# OLED-0_96-Demo-MCU_Board.net
KiCad netlist of a schematic drawn in Altium Designer
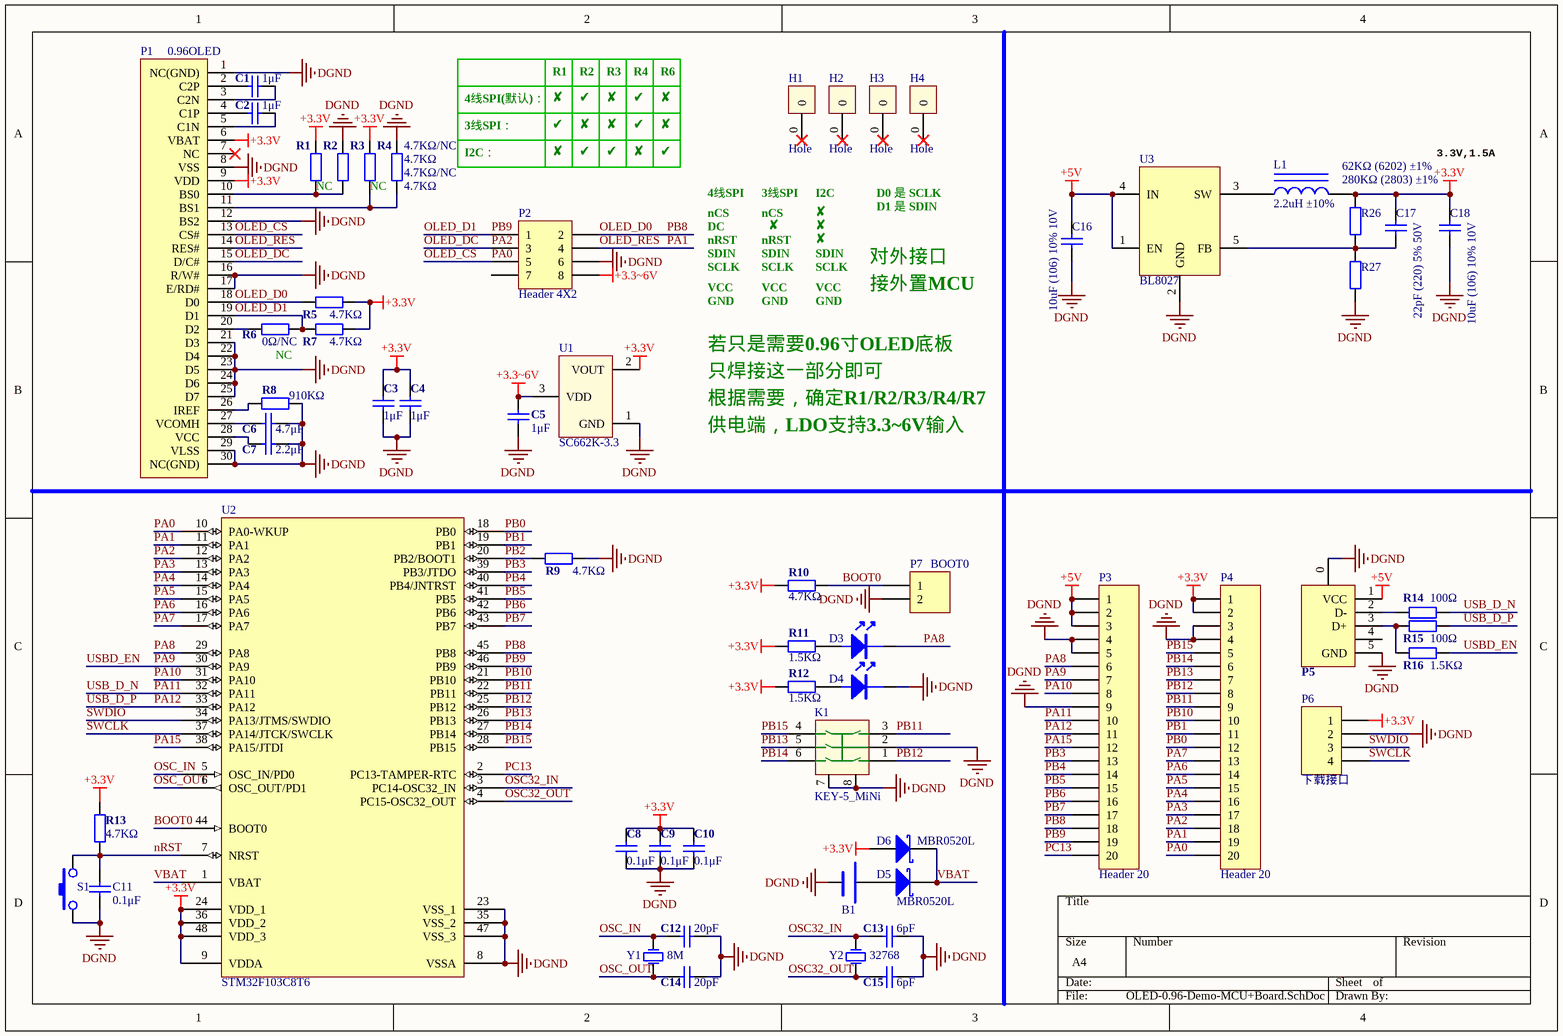
[diagram p0: OLED-0.96-Demo-MCU+Board.SchDoc]

(export (version "E")
  (design (tool "Eeschema 10.0.6"))
  (components
    (comp (ref "B1")
      (value "BAT")
      (footprint "BATTERY SOCKET")
      (description "电池")
      (libsource (lib "OLED-0.96-Demo-MCU+Board") (part "BAT"))
    )
    (comp (ref "C1")
      (value "1μF")
      (footprint "LC-0603_C")
      (description "贴片电容")
      (libsource (lib "FourAxis") (part "Cap"))
    )
    (comp (ref "C2")
      (value "1μF")
      (footprint "LC-0603_C")
      (description "贴片电容")
      (libsource (lib "FourAxis") (part "Cap"))
    )
    (comp (ref "C3")
      (value "1μF")
      (footprint "LC-0603_C")
      (description "贴片电容")
      (libsource (lib "FourAxis") (part "Cap"))
    )
    (comp (ref "C4")
      (value "1μF")
      (footprint "LC-0603_C")
      (description "贴片电容")
      (libsource (lib "FourAxis") (part "Cap"))
    )
    (comp (ref "C5")
      (value "1μF")
      (footprint "LC-0603_C")
      (description "贴片电容")
      (libsource (lib "FourAxis") (part "Cap"))
    )
    (comp (ref "C6")
      (value "4.7μF")
      (footprint "LC-0603_C")
      (description "贴片电容")
      (libsource (lib "FourAxis") (part "Cap"))
    )
    (comp (ref "C7")
      (value "2.2μF")
      (footprint "LC-0603_C")
      (description "贴片电容")
      (libsource (lib "FourAxis") (part "Cap"))
    )
    (comp (ref "C8")
      (value "0.1μF")
      (footprint "LC-0603_C")
      (description "贴片电容")
      (libsource (lib "FourAxis") (part "Cap"))
    )
    (comp (ref "C9")
      (value "0.1μF")
      (footprint "LC-0603_C")
      (description "贴片电容")
      (libsource (lib "FourAxis") (part "Cap"))
    )
    (comp (ref "C10")
      (value "0.1μF")
      (footprint "LC-0603_C")
      (description "贴片电容")
      (libsource (lib "FourAxis") (part "Cap"))
    )
    (comp (ref "C11")
      (value "0.1μF")
      (footprint "LC-0603_C")
      (description "贴片电容")
      (libsource (lib "FourAxis") (part "Cap"))
    )
    (comp (ref "C12")
      (value "20pF")
      (footprint "LC-0603_C")
      (description "贴片电容")
      (libsource (lib "FourAxis") (part "Cap"))
    )
    (comp (ref "C13")
      (value "6pF")
      (footprint "LC-0603_C")
      (description "贴片电容")
      (libsource (lib "FourAxis") (part "Cap"))
    )
    (comp (ref "C14")
      (value "20pF")
      (footprint "LC-0603_C")
      (description "贴片电容")
      (libsource (lib "FourAxis") (part "Cap"))
    )
    (comp (ref "C15")
      (value "6pF")
      (footprint "LC-0603_C")
      (description "贴片电容")
      (libsource (lib "FourAxis") (part "Cap"))
    )
    (comp (ref "C16")
      (value "10uF (106) 10% 10V")
      (footprint "LC-0603_C")
      (description "贴片电容")
      (libsource (lib "Miscellaneous Devices LC") (part "0603 10uF (106) 10% 10V"))
    )
    (comp (ref "C17")
      (value "22pF (220) 5% 50V")
      (footprint "LC-0603_C")
      (description "贴片电容")
      (libsource (lib "Miscellaneous Devices LC") (part "0402 22pF (220) 5% 50V"))
    )
    (comp (ref "C18")
      (value "10uF (106) 10% 10V")
      (footprint "LC-0603_C")
      (description "贴片电容")
      (libsource (lib "Miscellaneous Devices LC") (part "0603 10uF (106) 10% 10V"))
    )
    (comp (ref "D3")
      (value "POWER")
      (footprint "LC-0603_LED_S1")
      (description "发光二极管")
      (libsource (lib "OLED-0.96-Demo-MCU+Board") (part "LED1"))
    )
    (comp (ref "D4")
      (value "POWER")
      (footprint "LC-0603_LED_S1")
      (description "发光二极管")
      (libsource (lib "OLED-0.96-Demo-MCU+Board") (part "LED1"))
    )
    (comp (ref "D5")
      (value "MBR0520L")
      (footprint "LC-SOD-123")
      (description "贴片肖特基二极管")
      (fields (field (name "PUBLISHER") "Altium Limited"))
      (libsource (lib "USB-UART-RJ45") (part "Diode 18TQ045"))
    )
    (comp (ref "D6")
      (value "MBR0520L")
      (footprint "LC-SOD-123")
      (description "贴片肖特基二极管")
      (fields (field (name "PUBLISHER") "Altium Limited"))
      (libsource (lib "USB-UART-RJ45") (part "Diode 18TQ045"))
    )
    (comp (ref "H1")
      (value "Hole")
      (footprint "Hole")
      (description "螺丝孔")
      (libsource (lib "VGA_2") (part "Hole"))
    )
    (comp (ref "H2")
      (value "Hole")
      (footprint "Hole")
      (description "螺丝孔")
      (libsource (lib "VGA_2") (part "Hole"))
    )
    (comp (ref "H3")
      (value "Hole")
      (footprint "Hole")
      (description "螺丝孔")
      (libsource (lib "VGA_2") (part "Hole"))
    )
    (comp (ref "H4")
      (value "Hole")
      (footprint "Hole")
      (description "螺丝孔")
      (libsource (lib "VGA_2") (part "Hole"))
    )
    (comp (ref "K1")
      (value "KEY-5_MiNi")
      (footprint "KEY_5_mini")
      (description "贴片五向开关")
      (libsource (lib "OLED-0.96-Demo-MCU+Board") (part "KEY-5_MiNi"))
    )
    (comp (ref "L1")
      (value "2.2uH ±10%")
      (footprint "LC-0805_L")
      (description "贴片电感")
      (libsource (lib "Miscellaneous Devices LC") (part "0805 2.2uH 10%"))
    )
    (comp (ref "P1")
      (value "0.96OLED")
      (footprint "OLED_0.96")
      (description "接口")
      (fields (field (name "PUBLISHER") "Altium Limited"))
      (libsource (lib "HLW8012-Demo") (part "0.96OLED"))
    )
    (comp (ref "P2")
      (value "Header 4X2")
      (footprint "2*4P_SMT")
      (description "Header, 4-Pin, Dual row")
      (fields (field (name "PUBLISHER") "Altium Limited"))
      (libsource (lib "Miscellaneous Connectors") (part "Header 4X2"))
    )
    (comp (ref "P3")
      (value "Header 20")
      (footprint "HDR1X20")
      (description "Header, 20-Pin")
      (fields (field (name "PUBLISHER") "Altium Limited"))
      (libsource (lib "Miscellaneous Connectors") (part "Header 20"))
    )
    (comp (ref "P4")
      (value "Header 20")
      (footprint "HDR1X20")
      (description "Header, 20-Pin")
      (fields (field (name "PUBLISHER") "Altium Limited"))
      (libsource (lib "Miscellaneous Connectors") (part "Header 20"))
    )
    (comp (ref "P5")
      (value "Micro USB,母头")
      (footprint "MicroUSB2")
      (description "接口")
      (libsource (lib "SU-IOT_v2.0") (part "microUSB"))
    )
    (comp (ref "P6")
      (value "下载接口")
      (footprint "HDR1X4")
      (description "Header, 4-Pin")
      (fields (field (name "PUBLISHER") "Altium Limited"))
      (libsource (lib "Miscellaneous Connectors") (part "Header 4"))
    )
    (comp (ref "P7")
      (value "BOOT0")
      (footprint "HDR1X2")
      (description "Header, 2-Pin")
      (fields (field (name "PUBLISHER") "Altium Limited"))
      (libsource (lib "Miscellaneous Connectors") (part "Header 2"))
    )
    (comp (ref "R1")
      (value "4.7KΩ/NC")
      (footprint "LC-0603_R")
      (description "贴片电阻")
      (libsource (lib "") (part "电阻_2"))
    )
    (comp (ref "R2")
      (value "4.7KΩ")
      (footprint "LC-0603_R")
      (description "贴片电阻")
      (libsource (lib "") (part "电阻_2"))
    )
    (comp (ref "R3")
      (value "4.7KΩ/NC")
      (footprint "LC-0603_R")
      (description "贴片电阻")
      (libsource (lib "") (part "电阻_1"))
    )
    (comp (ref "R4")
      (value "4.7KΩ")
      (footprint "LC-0603_R")
      (description "贴片电阻")
      (libsource (lib "") (part "电阻_1"))
    )
    (comp (ref "R5")
      (value "4.7KΩ")
      (footprint "LC-0603_R")
      (description "贴片电阻")
      (libsource (lib "FourAxis") (part "电阻"))
    )
    (comp (ref "R6")
      (value "0Ω/NC")
      (footprint "LC-0603_R")
      (description "贴片电阻")
      (libsource (lib "") (part "电阻_1"))
    )
    (comp (ref "R7")
      (value "4.7KΩ")
      (footprint "LC-0603_R")
      (description "贴片电阻")
      (libsource (lib "FourAxis") (part "电阻"))
    )
    (comp (ref "R8")
      (value "910KΩ")
      (footprint "LC-0603_R")
      (description "贴片电阻")
      (libsource (lib "") (part "电阻_1"))
    )
    (comp (ref "R9")
      (value "4.7KΩ")
      (footprint "LC-0603_R")
      (description "贴片电阻")
      (libsource (lib "FourAxis") (part "电阻"))
    )
    (comp (ref "R10")
      (value "4.7KΩ")
      (footprint "LC-0603_R")
      (description "贴片电阻")
      (libsource (lib "FourAxis") (part "电阻"))
    )
    (comp (ref "R11")
      (value "1.5KΩ")
      (footprint "LC-0603_R")
      (description "贴片电阻")
      (libsource (lib "FourAxis") (part "电阻"))
    )
    (comp (ref "R12")
      (value "1.5KΩ")
      (footprint "LC-0603_R")
      (description "贴片电阻")
      (libsource (lib "FourAxis") (part "电阻"))
    )
    (comp (ref "R13")
      (value "4.7KΩ")
      (footprint "LC-0603_R")
      (description "贴片电阻")
      (libsource (lib "") (part "电阻_2"))
    )
    (comp (ref "R14")
      (value "100Ω")
      (footprint "LC-0603_R")
      (description "贴片电阻")
      (libsource (lib "FourAxis") (part "电阻"))
    )
    (comp (ref "R15")
      (value "100Ω")
      (footprint "LC-0603_R")
      (description "贴片电阻")
      (libsource (lib "FourAxis") (part "电阻"))
    )
    (comp (ref "R16")
      (value "1.5KΩ")
      (footprint "LC-0603_R")
      (description "贴片电阻")
      (libsource (lib "FourAxis") (part "电阻"))
    )
    (comp (ref "R26")
      (value "280KΩ (2803) ±1%")
      (footprint "LC-0603_R")
      (description "贴片电阻")
      (libsource (lib "") (part "0805 62KΩ (6202) 1%_1"))
    )
    (comp (ref "R27")
      (value "62KΩ (6202) ±1%")
      (footprint "LC-0603_R")
      (description "贴片电阻")
      (libsource (lib "Miscellaneous Devices LC") (part "0805 62KΩ (6202) 1%"))
    )
    (comp (ref "S1")
      (value "微动开关")
      (footprint "按键")
      (libsource (lib "OLED-0.96-Demo-MCU+Board") (part "微动开关"))
    )
    (comp (ref "U1")
      (value "SC662K-3.3")
      (footprint "LC-SOT-23(SOT-23-3)")
      (description "IC")
      (libsource (lib "HLW8012-Demo") (part "SC662K-3.3"))
    )
    (comp (ref "U2")
      (value "STM32F103C8T6")
      (footprint "LC-LQFP-48_7x7x05P")
      (description "IC")
      (fields (field (name "PUBLISHER") "Altium Limited"))
      (libsource (lib "FourAxis") (part "STM32F103CBT6"))
    )
    (comp (ref "U3")
      (value "BL8027")
      (footprint "LC-SOT-23-5")
      (description "IC")
      (libsource (lib "OLED-0.96-Demo-MCU+Board") (part "DC-DC"))
    )
    (comp (ref "Y1")
      (value "8M")
      (footprint "LC-HC-49SMD")
      (description "晶振（直插）")
      (fields (field (name "PUBLISHER") "Altium Limited"))
      (libsource (lib "") (part "XTAL_1_1"))
    )
    (comp (ref "Y2")
      (value "32768")
      (footprint "MC-306")
      (description "晶振（直插）")
      (fields (field (name "PUBLISHER") "Altium Limited"))
      (libsource (lib "OLED-0.96-Demo-MCU+Board") (part "XTAL_1"))
    )
  )
  (nets
    (net (code "1") (name "+3.3V") (class "Default")
      (node (ref "C10") (pin "2") (pinfunction "2_2") (pintype "passive"))
      (node (ref "C17") (pin "2") (pinfunction "2_2") (pintype "passive"))
      (node (ref "C18") (pin "2") (pinfunction "2_2") (pintype "passive"))
      (node (ref "C3") (pin "2") (pinfunction "2_2") (pintype "passive"))
      (node (ref "C4") (pin "2") (pinfunction "2_2") (pintype "passive"))
      (node (ref "C8") (pin "2") (pinfunction "2_2") (pintype "passive"))
      (node (ref "C9") (pin "2") (pinfunction "2_2") (pintype "passive"))
      (node (ref "D6") (pin "1") (pinfunction "A_1") (pintype "passive"))
      (node (ref "L1") (pin "2") (pinfunction "2_2") (pintype "passive"))
      (node (ref "P1") (pin "6") (pinfunction "VBAT_6") (pintype "passive"))
      (node (ref "P1") (pin "9") (pinfunction "VDD_9") (pintype "passive"))
      (node (ref "P4") (pin "1") (pinfunction "1_1") (pintype "passive"))
      (node (ref "P4") (pin "2") (pinfunction "2_2") (pintype "passive"))
      (node (ref "P6") (pin "1") (pinfunction "1_1") (pintype "passive"))
      (node (ref "R1") (pin "2") (pinfunction "2_2") (pintype "passive"))
      (node (ref "R10") (pin "2") (pinfunction "2_2") (pintype "passive"))
      (node (ref "R11") (pin "2") (pinfunction "2_2") (pintype "passive"))
      (node (ref "R12") (pin "2") (pinfunction "2_2") (pintype "passive"))
      (node (ref "R13") (pin "2") (pinfunction "2_2") (pintype "passive"))
      (node (ref "R26") (pin "1") (pinfunction "1_1") (pintype "passive"))
      (node (ref "R3") (pin "1") (pinfunction "1_1") (pintype "passive"))
      (node (ref "R5") (pin "1") (pinfunction "1_1") (pintype "passive"))
      (node (ref "R7") (pin "1") (pinfunction "1_1") (pintype "passive"))
      (node (ref "U1") (pin "2") (pinfunction "VOUT_2") (pintype "passive"))
      (node (ref "U2") (pin "24") (pinfunction "VDD_1_24") (pintype "power_in"))
      (node (ref "U2") (pin "36") (pinfunction "VDD_2_36") (pintype "power_in"))
      (node (ref "U2") (pin "48") (pinfunction "VDD_3_48") (pintype "power_in"))
      (node (ref "U2") (pin "9") (pinfunction "VDDA_9") (pintype "power_in"))
    )
    (net (code "2") (name "+3.3~6V") (class "Default")
      (node (ref "C5") (pin "1") (pinfunction "1_1") (pintype "passive"))
      (node (ref "P2") (pin "8") (pinfunction "8_8") (pintype "passive"))
      (node (ref "U1") (pin "3") (pinfunction "VDD_3") (pintype "passive"))
    )
    (net (code "3") (name "+5V") (class "Default")
      (node (ref "C16") (pin "2") (pinfunction "2_2") (pintype "passive"))
      (node (ref "P3") (pin "1") (pinfunction "1_1") (pintype "passive"))
      (node (ref "P3") (pin "2") (pinfunction "2_2") (pintype "passive"))
      (node (ref "P3") (pin "3") (pinfunction "3_3") (pintype "passive"))
      (node (ref "P5") (pin "1") (pinfunction "VCC_1") (pintype "passive"))
      (node (ref "U3") (pin "1") (pinfunction "EN_1") (pintype "passive"))
      (node (ref "U3") (pin "4") (pinfunction "IN_4") (pintype "passive"))
    )
    (net (code "4") (name "/BOOT0") (class "Default")
      (node (ref "P7") (pin "1") (pinfunction "1_1") (pintype "passive"))
      (node (ref "R10") (pin "1") (pinfunction "1_1") (pintype "passive"))
      (node (ref "U2") (pin "44") (pinfunction "BOOT0_44") (pintype "input"))
    )
    (net (code "5") (name "/OLED_CS") (class "Default")
      (node (ref "P1") (pin "13") (pinfunction "CS#_13") (pintype "passive"))
      (node (ref "P2") (pin "5") (pinfunction "5_5") (pintype "passive"))
      (node (ref "P4") (pin "20") (pinfunction "20_20") (pintype "passive"))
      (node (ref "U2") (pin "10") (pinfunction "PA0-WKUP_10") (pintype "bidirectional"))
    )
    (net (code "6") (name "/OLED_D0") (class "Default")
      (node (ref "P1") (pin "18") (pinfunction "D0_18") (pintype "passive"))
      (node (ref "P2") (pin "2") (pinfunction "2_2") (pintype "passive"))
      (node (ref "P3") (pin "18") (pinfunction "18_18") (pintype "passive"))
      (node (ref "R5") (pin "2") (pinfunction "2_2") (pintype "passive"))
      (node (ref "U2") (pin "45") (pinfunction "PB8_45") (pintype "bidirectional"))
    )
    (net (code "7") (name "/OLED_D1") (class "Default")
      (node (ref "P1") (pin "19") (pinfunction "D1_19") (pintype "passive"))
      (node (ref "P2") (pin "1") (pinfunction "1_1") (pintype "passive"))
      (node (ref "P3") (pin "19") (pinfunction "19_19") (pintype "passive"))
      (node (ref "R6") (pin "1") (pinfunction "1_1") (pintype "passive"))
      (node (ref "R7") (pin "2") (pinfunction "2_2") (pintype "passive"))
      (node (ref "U2") (pin "46") (pinfunction "PB9_46") (pintype "bidirectional"))
    )
    (net (code "8") (name "/OLED_DC") (class "Default")
      (node (ref "P1") (pin "15") (pinfunction "D/C#_15") (pintype "passive"))
      (node (ref "P2") (pin "3") (pinfunction "3_3") (pintype "passive"))
      (node (ref "P4") (pin "18") (pinfunction "18_18") (pintype "passive"))
      (node (ref "U2") (pin "12") (pinfunction "PA2_12") (pintype "bidirectional"))
    )
    (net (code "9") (name "/OLED_RES") (class "Default")
      (node (ref "P1") (pin "14") (pinfunction "RES#_14") (pintype "passive"))
      (node (ref "P2") (pin "4") (pinfunction "4_4") (pintype "passive"))
      (node (ref "P4") (pin "19") (pinfunction "19_19") (pintype "passive"))
      (node (ref "U2") (pin "11") (pinfunction "PA1_11") (pintype "bidirectional"))
    )
    (net (code "10") (name "/OSC32_IN") (class "Default")
      (node (ref "C13") (pin "1") (pinfunction "1_1") (pintype "passive"))
      (node (ref "U2") (pin "3") (pinfunction "PC14-OSC32_IN_3") (pintype "bidirectional"))
      (node (ref "Y2") (pin "1") (pinfunction "1_1") (pintype "passive"))
    )
    (net (code "11") (name "/OSC32_OUT") (class "Default")
      (node (ref "C15") (pin "1") (pinfunction "1_1") (pintype "passive"))
      (node (ref "U2") (pin "4") (pinfunction "PC15-OSC32_OUT_4") (pintype "bidirectional"))
      (node (ref "Y2") (pin "4") (pinfunction "4_4") (pintype "passive"))
    )
    (net (code "12") (name "/OSC_IN") (class "Default")
      (node (ref "C12") (pin "1") (pinfunction "1_1") (pintype "passive"))
      (node (ref "U2") (pin "5") (pinfunction "OSC_IN/PD0_5") (pintype "input"))
      (node (ref "Y1") (pin "1") (pinfunction "1_1") (pintype "passive"))
    )
    (net (code "13") (name "/OSC_OUT") (class "Default")
      (node (ref "C14") (pin "1") (pinfunction "1_1") (pintype "passive"))
      (node (ref "U2") (pin "6") (pinfunction "OSC_OUT/PD1_6") (pintype "output"))
      (node (ref "Y1") (pin "2") (pinfunction "2_2") (pintype "passive"))
    )
    (net (code "14") (name "/PA3") (class "Default")
      (node (ref "P4") (pin "17") (pinfunction "17_17") (pintype "passive"))
      (node (ref "U2") (pin "13") (pinfunction "PA3_13") (pintype "bidirectional"))
    )
    (net (code "15") (name "/PA4") (class "Default")
      (node (ref "P4") (pin "16") (pinfunction "16_16") (pintype "passive"))
      (node (ref "U2") (pin "14") (pinfunction "PA4_14") (pintype "bidirectional"))
    )
    (net (code "16") (name "/PA5") (class "Default")
      (node (ref "P4") (pin "15") (pinfunction "15_15") (pintype "passive"))
      (node (ref "U2") (pin "15") (pinfunction "PA5_15") (pintype "bidirectional"))
    )
    (net (code "17") (name "/PA6") (class "Default")
      (node (ref "P4") (pin "14") (pinfunction "14_14") (pintype "passive"))
      (node (ref "U2") (pin "16") (pinfunction "PA6_16") (pintype "bidirectional"))
    )
    (net (code "18") (name "/PA7") (class "Default")
      (node (ref "P4") (pin "13") (pinfunction "13_13") (pintype "passive"))
      (node (ref "U2") (pin "17") (pinfunction "PA7_17") (pintype "bidirectional"))
    )
    (net (code "19") (name "/PA8") (class "Default")
      (node (ref "D3") (pin "K") (pinfunction "K_K") (pintype "passive"))
      (node (ref "P3") (pin "6") (pinfunction "6_6") (pintype "passive"))
      (node (ref "U2") (pin "29") (pinfunction "PA8_29") (pintype "bidirectional"))
    )
    (net (code "20") (name "/PA9") (class "Default")
      (node (ref "P3") (pin "7") (pinfunction "7_7") (pintype "passive"))
      (node (ref "R16") (pin "1") (pinfunction "1_1") (pintype "passive"))
      (node (ref "U2") (pin "30") (pinfunction "PA9_30") (pintype "bidirectional"))
    )
    (net (code "21") (name "/PA10") (class "Default")
      (node (ref "P3") (pin "8") (pinfunction "8_8") (pintype "passive"))
      (node (ref "U2") (pin "31") (pinfunction "PA10_31") (pintype "bidirectional"))
    )
    (net (code "22") (name "/PA11") (class "Default")
      (node (ref "P3") (pin "10") (pinfunction "10_10") (pintype "passive"))
      (node (ref "R14") (pin "1") (pinfunction "1_1") (pintype "passive"))
      (node (ref "U2") (pin "32") (pinfunction "PA11_32") (pintype "bidirectional"))
    )
    (net (code "23") (name "/PA12") (class "Default")
      (node (ref "P3") (pin "11") (pinfunction "11_11") (pintype "passive"))
      (node (ref "R15") (pin "1") (pinfunction "1_1") (pintype "passive"))
      (node (ref "U2") (pin "33") (pinfunction "PA12_33") (pintype "bidirectional"))
    )
    (net (code "24") (name "/PA15") (class "Default")
      (node (ref "P3") (pin "12") (pinfunction "12_12") (pintype "passive"))
      (node (ref "U2") (pin "38") (pinfunction "PA15/JTDI_38") (pintype "bidirectional"))
    )
    (net (code "25") (name "/PB0") (class "Default")
      (node (ref "P4") (pin "12") (pinfunction "12_12") (pintype "passive"))
      (node (ref "U2") (pin "18") (pinfunction "PB0_18") (pintype "bidirectional"))
    )
    (net (code "26") (name "/PB1") (class "Default")
      (node (ref "P4") (pin "11") (pinfunction "11_11") (pintype "passive"))
      (node (ref "U2") (pin "19") (pinfunction "PB1_19") (pintype "bidirectional"))
    )
    (net (code "27") (name "/PB2") (class "Default")
      (node (ref "R9") (pin "2") (pinfunction "2_2") (pintype "passive"))
      (node (ref "U2") (pin "20") (pinfunction "PB2/BOOT1_20") (pintype "bidirectional"))
    )
    (net (code "28") (name "/PB3") (class "Default")
      (node (ref "P3") (pin "13") (pinfunction "13_13") (pintype "passive"))
      (node (ref "U2") (pin "39") (pinfunction "PB3/JTDO_39") (pintype "bidirectional"))
    )
    (net (code "29") (name "/PB4") (class "Default")
      (node (ref "P3") (pin "14") (pinfunction "14_14") (pintype "passive"))
      (node (ref "U2") (pin "40") (pinfunction "PB4/JNTRST_40") (pintype "bidirectional"))
    )
    (net (code "30") (name "/PB5") (class "Default")
      (node (ref "P3") (pin "15") (pinfunction "15_15") (pintype "passive"))
      (node (ref "U2") (pin "41") (pinfunction "PB5_41") (pintype "bidirectional"))
    )
    (net (code "31") (name "/PB6") (class "Default")
      (node (ref "P3") (pin "16") (pinfunction "16_16") (pintype "passive"))
      (node (ref "U2") (pin "42") (pinfunction "PB6_42") (pintype "bidirectional"))
    )
    (net (code "32") (name "/PB7") (class "Default")
      (node (ref "P3") (pin "17") (pinfunction "17_17") (pintype "passive"))
      (node (ref "U2") (pin "43") (pinfunction "PB7_43") (pintype "bidirectional"))
    )
    (net (code "33") (name "/PB10") (class "Default")
      (node (ref "P4") (pin "10") (pinfunction "10_10") (pintype "passive"))
      (node (ref "U2") (pin "21") (pinfunction "PB10_21") (pintype "bidirectional"))
    )
    (net (code "34") (name "/PB11") (class "Default")
      (node (ref "K1") (pin "3") (pintype "passive"))
      (node (ref "P4") (pin "9") (pinfunction "9_9") (pintype "passive"))
      (node (ref "U2") (pin "22") (pinfunction "PB11_22") (pintype "bidirectional"))
    )
    (net (code "35") (name "/PB12") (class "Default")
      (node (ref "K1") (pin "1") (pintype "passive"))
      (node (ref "P4") (pin "8") (pinfunction "8_8") (pintype "passive"))
      (node (ref "U2") (pin "25") (pinfunction "PB12_25") (pintype "bidirectional"))
    )
    (net (code "36") (name "/PB13") (class "Default")
      (node (ref "K1") (pin "5") (pintype "passive"))
      (node (ref "P4") (pin "7") (pinfunction "7_7") (pintype "passive"))
      (node (ref "U2") (pin "26") (pinfunction "PB13_26") (pintype "bidirectional"))
    )
    (net (code "37") (name "/PB14") (class "Default")
      (node (ref "K1") (pin "6") (pintype "passive"))
      (node (ref "P4") (pin "6") (pinfunction "6_6") (pintype "passive"))
      (node (ref "U2") (pin "27") (pinfunction "PB14_27") (pintype "bidirectional"))
    )
    (net (code "38") (name "/PB15") (class "Default")
      (node (ref "K1") (pin "4") (pintype "passive"))
      (node (ref "P4") (pin "5") (pinfunction "5_5") (pintype "passive"))
      (node (ref "U2") (pin "28") (pinfunction "PB15_28") (pintype "bidirectional"))
    )
    (net (code "39") (name "/PC13") (class "Default")
      (node (ref "P3") (pin "20") (pinfunction "20_20") (pintype "passive"))
      (node (ref "U2") (pin "2") (pinfunction "PC13-TAMPER-RTC_2") (pintype "bidirectional"))
    )
    (net (code "40") (name "/SWCLK") (class "Default")
      (node (ref "P6") (pin "4") (pinfunction "4_4") (pintype "passive"))
      (node (ref "U2") (pin "37") (pinfunction "PA14/JTCK/SWCLK_37") (pintype "bidirectional"))
    )
    (net (code "41") (name "/SWDIO") (class "Default")
      (node (ref "P6") (pin "3") (pinfunction "3_3") (pintype "passive"))
      (node (ref "U2") (pin "34") (pinfunction "PA13/JTMS/SWDIO_34") (pintype "bidirectional"))
    )
    (net (code "42") (name "/VBAT") (class "Default")
      (node (ref "D5") (pin "2") (pinfunction "K_2") (pintype "passive"))
      (node (ref "D6") (pin "2") (pinfunction "K_2") (pintype "passive"))
      (node (ref "U2") (pin "1") (pinfunction "VBAT_1") (pintype "power_in"))
    )
    (net (code "43") (name "/nRST") (class "Default")
      (node (ref "C11") (pin "2") (pinfunction "2_2") (pintype "passive"))
      (node (ref "R13") (pin "1") (pinfunction "1_1") (pintype "passive"))
      (node (ref "S1") (pin "2") (pinfunction "2_2") (pintype "passive"))
      (node (ref "U2") (pin "7") (pinfunction "NRST_7") (pintype "bidirectional"))
    )
    (net (code "44") (name "DGND") (class "Default")
      (node (ref "B1") (pin "2") (pinfunction "2_2") (pintype "passive"))
      (node (ref "C10") (pin "1") (pinfunction "1_1") (pintype "passive"))
      (node (ref "C11") (pin "1") (pinfunction "1_1") (pintype "passive"))
      (node (ref "C12") (pin "2") (pinfunction "2_2") (pintype "passive"))
      (node (ref "C13") (pin "2") (pinfunction "2_2") (pintype "passive"))
      (node (ref "C14") (pin "2") (pinfunction "2_2") (pintype "passive"))
      (node (ref "C15") (pin "2") (pinfunction "2_2") (pintype "passive"))
      (node (ref "C16") (pin "1") (pinfunction "1_1") (pintype "passive"))
      (node (ref "C18") (pin "1") (pinfunction "1_1") (pintype "passive"))
      (node (ref "C3") (pin "1") (pinfunction "1_1") (pintype "passive"))
      (node (ref "C4") (pin "1") (pinfunction "1_1") (pintype "passive"))
      (node (ref "C5") (pin "2") (pinfunction "2_2") (pintype "passive"))
      (node (ref "C6") (pin "1") (pinfunction "1_1") (pintype "passive"))
      (node (ref "C7") (pin "1") (pinfunction "1_1") (pintype "passive"))
      (node (ref "C8") (pin "1") (pinfunction "1_1") (pintype "passive"))
      (node (ref "C9") (pin "1") (pinfunction "1_1") (pintype "passive"))
      (node (ref "D4") (pin "K") (pinfunction "K_K") (pintype "passive"))
      (node (ref "K1") (pin "2") (pintype "passive"))
      (node (ref "K1") (pin "7") (pinfunction "7_7") (pintype "passive"))
      (node (ref "K1") (pin "8") (pinfunction "8_8") (pintype "passive"))
      (node (ref "P1") (pin "1") (pinfunction "NC(GND)_1") (pintype "passive"))
      (node (ref "P1") (pin "12") (pinfunction "BS2_12") (pintype "passive"))
      (node (ref "P1") (pin "16") (pinfunction "R/W#_16") (pintype "passive"))
      (node (ref "P1") (pin "17") (pinfunction "E/RD#_17") (pintype "passive"))
      (node (ref "P1") (pin "21") (pinfunction "D3_21") (pintype "passive"))
      (node (ref "P1") (pin "22") (pinfunction "D4_22") (pintype "passive"))
      (node (ref "P1") (pin "23") (pinfunction "D5_23") (pintype "passive"))
      (node (ref "P1") (pin "24") (pinfunction "D6_24") (pintype "passive"))
      (node (ref "P1") (pin "25") (pinfunction "D7_25") (pintype "passive"))
      (node (ref "P1") (pin "29") (pinfunction "VLSS_29") (pintype "passive"))
      (node (ref "P1") (pin "30") (pinfunction "NC(GND)_30") (pintype "passive"))
      (node (ref "P1") (pin "8") (pinfunction "VSS_8") (pintype "passive"))
      (node (ref "P2") (pin "6") (pinfunction "6_6") (pintype "passive"))
      (node (ref "P3") (pin "4") (pinfunction "4_4") (pintype "passive"))
      (node (ref "P3") (pin "5") (pinfunction "5_5") (pintype "passive"))
      (node (ref "P3") (pin "9") (pinfunction "9_9") (pintype "passive"))
      (node (ref "P4") (pin "3") (pinfunction "3_3") (pintype "passive"))
      (node (ref "P4") (pin "4") (pinfunction "4_4") (pintype "passive"))
      (node (ref "P5") (pin "0") (pinfunction "GND_0") (pintype "passive"))
      (node (ref "P5") (pin "5") (pinfunction "GND_5") (pintype "passive"))
      (node (ref "P6") (pin "2") (pinfunction "2_2") (pintype "passive"))
      (node (ref "P7") (pin "2") (pinfunction "2_2") (pintype "passive"))
      (node (ref "R2") (pin "2") (pinfunction "2_2") (pintype "passive"))
      (node (ref "R27") (pin "1") (pinfunction "1_1") (pintype "passive"))
      (node (ref "R4") (pin "1") (pinfunction "1_1") (pintype "passive"))
      (node (ref "R8") (pin "1") (pinfunction "1_1") (pintype "passive"))
      (node (ref "R9") (pin "1") (pinfunction "1_1") (pintype "passive"))
      (node (ref "S1") (pin "1") (pinfunction "1_1") (pintype "passive"))
      (node (ref "U1") (pin "1") (pinfunction "GND_1") (pintype "passive"))
      (node (ref "U2") (pin "23") (pinfunction "VSS_1_23") (pintype "power_in"))
      (node (ref "U2") (pin "35") (pinfunction "VSS_2_35") (pintype "power_in"))
      (node (ref "U2") (pin "47") (pinfunction "VSS_3_47") (pintype "power_in"))
      (node (ref "U2") (pin "8") (pinfunction "VSSA_8") (pintype "power_in"))
      (node (ref "U3") (pin "2") (pinfunction "GND_2") (pintype "passive"))
    )
    (net (code "45") (name "Net-(D3-PadA)") (class "Default")
      (node (ref "D3") (pin "A") (pinfunction "A_A") (pintype "passive"))
      (node (ref "R11") (pin "1") (pinfunction "1_1") (pintype "passive"))
    )
    (net (code "46") (name "Net-(D4-PadA)") (class "Default")
      (node (ref "D4") (pin "A") (pinfunction "A_A") (pintype "passive"))
      (node (ref "R12") (pin "1") (pinfunction "1_1") (pintype "passive"))
    )
    (net (code "47") (name "Net-(D5-A)") (class "Default")
      (node (ref "B1") (pin "1") (pinfunction "1_1") (pintype "passive"))
      (node (ref "D5") (pin "1") (pinfunction "A_1") (pintype "passive"))
    )
    (net (code "48") (name "Net-(P1-BS0)") (class "Default")
      (node (ref "P1") (pin "10") (pinfunction "BS0_10") (pintype "passive"))
      (node (ref "R1") (pin "1") (pinfunction "1_1") (pintype "passive"))
      (node (ref "R2") (pin "1") (pinfunction "1_1") (pintype "passive"))
    )
    (net (code "49") (name "Net-(P1-BS1)") (class "Default")
      (node (ref "P1") (pin "11") (pinfunction "BS1_11") (pintype "passive"))
      (node (ref "R3") (pin "2") (pinfunction "2_2") (pintype "passive"))
      (node (ref "R4") (pin "2") (pinfunction "2_2") (pintype "passive"))
    )
    (net (code "50") (name "Net-(P1-C1N)") (class "Default")
      (node (ref "C2") (pin "1") (pinfunction "1_1") (pintype "passive"))
      (node (ref "P1") (pin "5") (pinfunction "C1N_5") (pintype "passive"))
    )
    (net (code "51") (name "Net-(P1-C1P)") (class "Default")
      (node (ref "C2") (pin "2") (pinfunction "2_2") (pintype "passive"))
      (node (ref "P1") (pin "4") (pinfunction "C1P_4") (pintype "passive"))
    )
    (net (code "52") (name "Net-(P1-C2N)") (class "Default")
      (node (ref "C1") (pin "1") (pinfunction "1_1") (pintype "passive"))
      (node (ref "P1") (pin "3") (pinfunction "C2N_3") (pintype "passive"))
    )
    (net (code "53") (name "Net-(P1-C2P)") (class "Default")
      (node (ref "C1") (pin "2") (pinfunction "2_2") (pintype "passive"))
      (node (ref "P1") (pin "2") (pinfunction "C2P_2") (pintype "passive"))
    )
    (net (code "54") (name "Net-(P1-D2)") (class "Default")
      (node (ref "P1") (pin "20") (pinfunction "D2_20") (pintype "passive"))
      (node (ref "R6") (pin "2") (pinfunction "2_2") (pintype "passive"))
    )
    (net (code "55") (name "Net-(P1-IREF)") (class "Default")
      (node (ref "P1") (pin "26") (pinfunction "IREF_26") (pintype "passive"))
      (node (ref "R8") (pin "2") (pinfunction "2_2") (pintype "passive"))
    )
    (net (code "56") (name "Net-(P1-VCC)") (class "Default")
      (node (ref "C7") (pin "2") (pinfunction "2_2") (pintype "passive"))
      (node (ref "P1") (pin "28") (pinfunction "VCC_28") (pintype "passive"))
    )
    (net (code "57") (name "Net-(P1-VCOMH)") (class "Default")
      (node (ref "C6") (pin "2") (pinfunction "2_2") (pintype "passive"))
      (node (ref "P1") (pin "27") (pinfunction "VCOMH_27") (pintype "passive"))
    )
    (net (code "58") (name "Net-(P5-D+)") (class "Default")
      (node (ref "P5") (pin "3") (pinfunction "D+_3") (pintype "passive"))
      (node (ref "R15") (pin "2") (pinfunction "2_2") (pintype "passive"))
      (node (ref "R16") (pin "2") (pinfunction "2_2") (pintype "passive"))
    )
    (net (code "59") (name "Net-(P5-D-)") (class "Default")
      (node (ref "P5") (pin "2") (pinfunction "D-_2") (pintype "passive"))
      (node (ref "R14") (pin "2") (pinfunction "2_2") (pintype "passive"))
    )
    (net (code "60") (name "Net-(U3-FB)") (class "Default")
      (node (ref "C17") (pin "1") (pinfunction "1_1") (pintype "passive"))
      (node (ref "R26") (pin "2") (pinfunction "2_2") (pintype "passive"))
      (node (ref "R27") (pin "2") (pinfunction "2_2") (pintype "passive"))
      (node (ref "U3") (pin "5") (pinfunction "FB_5") (pintype "passive"))
    )
    (net (code "61") (name "Net-(U3-SW)") (class "Default")
      (node (ref "L1") (pin "1") (pinfunction "1_1") (pintype "passive"))
      (node (ref "U3") (pin "3") (pinfunction "SW_3") (pintype "passive"))
    )
    (net (code "62") (name "unconnected-(H1-Pad0)") (class "Default")
      (node (ref "H1") (pin "0") (pinfunction "0_0") (pintype "passive+no_connect"))
    )
    (net (code "63") (name "unconnected-(H2-Pad0)") (class "Default")
      (node (ref "H2") (pin "0") (pinfunction "0_0") (pintype "passive+no_connect"))
    )
    (net (code "64") (name "unconnected-(H3-Pad0)") (class "Default")
      (node (ref "H3") (pin "0") (pinfunction "0_0") (pintype "passive+no_connect"))
    )
    (net (code "65") (name "unconnected-(H4-Pad0)") (class "Default")
      (node (ref "H4") (pin "0") (pinfunction "0_0") (pintype "passive+no_connect"))
    )
    (net (code "66") (name "unconnected-(P1-NC-Pad7)") (class "Default")
      (node (ref "P1") (pin "7") (pinfunction "NC_7") (pintype "passive+no_connect"))
    )
    (net (code "67") (name "unconnected-(P2-Pad7)") (class "Default")
      (node (ref "P2") (pin "7") (pinfunction "7_7") (pintype "passive"))
    )
    (net (code "68") (name "unconnected-(P5-Pad4)") (class "Default")
      (node (ref "P5") (pin "4") (pintype "passive"))
    )
  )
)
